# Hum_ADC.net
KiCad netlist of a schematic drawn in Altium Designer
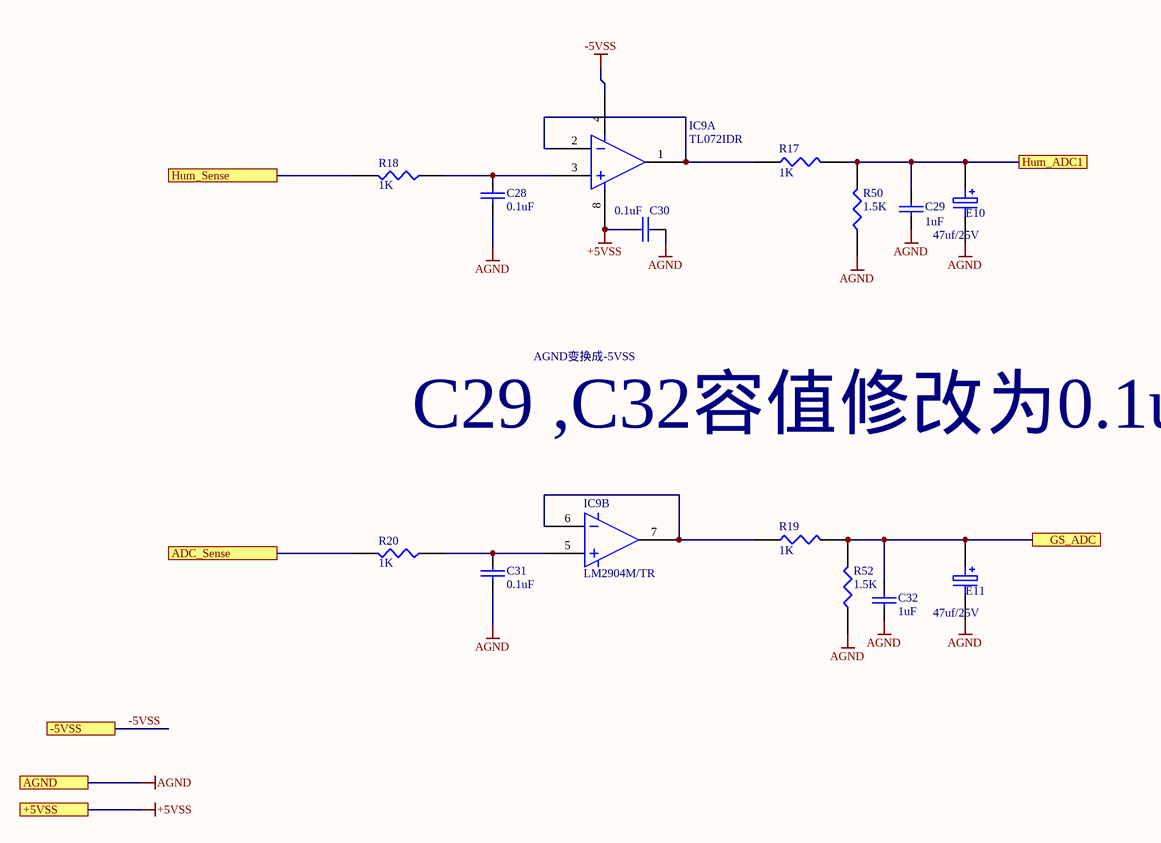
[diagram p0: Hum_ADC.SchDoc]

(export (version "E")
  (design (tool "Eeschema 10.0.6"))
  (components
    (comp (ref "C28")
      (value "0.1uF")
      (footprint "0805C")
      (description "品牌： SAMSUNG(三星) 型号： CL21B104KBCNNNC ：容值：100nF 精度：±10% 额定电压：50V 材质(温度系数)：X7R 材质:X7R")
      (libsource (lib "*") (part "CAP"))
    )
    (comp (ref "C29")
      (value "1uF")
      (footprint "0805C")
      (description "品牌： SAMSUNG(三星) 型号： CL21B104KBCNNNC ：容值：100nF 精度：±10% 额定电压：50V 材质(温度系数)：X7R 材质:X7R")
      (libsource (lib "*") (part "CAP"))
    )
    (comp (ref "C30")
      (value "0.1uF")
      (footprint "0805C")
      (description "品牌： SAMSUNG(三星) 型号： CL21B104KBCNNNC ：容值：100nF 精度：±10% 额定电压：50V 材质(温度系数)：X7R 材质:X7R")
      (libsource (lib "*") (part "CAP"))
    )
    (comp (ref "C31")
      (value "0.1uF")
      (footprint "0805C")
      (description "品牌： SAMSUNG(三星) 型号： CL21B104KBCNNNC ：容值：100nF 精度：±10% 额定电压：50V 材质(温度系数)：X7R 材质:X7R")
      (libsource (lib "*") (part "CAP"))
    )
    (comp (ref "C32")
      (value "1uF")
      (footprint "0805C")
      (description "品牌： SAMSUNG(三星) 型号： CL21B104KBCNNNC ：容值：100nF 精度：±10% 额定电压：50V 材质(温度系数)：X7R 材质:X7R")
      (libsource (lib "*") (part "CAP"))
    )
    (comp (ref "E10")
      (value "47uf/25V")
      (footprint "CAP-TH_BD5.0-P2.00-D0.8-FD")
      (description "品牌： CX(承兴) 型号： KM108M025G17RR0VH2FP0 容值：1000uF 精度：±20% 额定电压：25V")
      (libsource (lib "*") (part "ELECTRO1"))
    )
    (comp (ref "E11")
      (value "47uf/25V")
      (footprint "CAP-TH_BD5.0-P2.00-D0.8-FD")
      (description "品牌： CX(承兴) 型号： KM108M025G17RR0VH2FP0 容值：1000uF 精度：±20% 额定电压：25V")
      (libsource (lib "*") (part "ELECTRO1"))
    )
    (comp (ref "IC9")
      (value "TL072IDR")
      (footprint "LM2904M/TR")
      (description "品牌： HGSEMI(华冠)   型号： LM2904M/TR")
      (libsource (lib "main board fo stk_1") (part "TL072"))
    )
    (comp (ref "R17")
      (value "1K")
      (footprint "0805R")
      (description "品牌： UNI-ROYAL(厚声) 型号： 0805W8F1001T5E 电阻类型：厚膜电阻 阻值：1kΩ 精度：±1% 功率：125mW 温度系数：±100ppm/℃")
      (libsource (lib "*") (part "RES1"))
    )
    (comp (ref "R18")
      (value "1K")
      (footprint "0805R")
      (description "品牌： UNI-ROYAL(厚声) 型号： 0805W8F1001T5E 电阻类型：厚膜电阻 阻值：1kΩ 精度：±1% 功率：125mW 温度系数：±100ppm/℃")
      (libsource (lib "*") (part "RES1"))
    )
    (comp (ref "R19")
      (value "1K")
      (footprint "0805R")
      (description "品牌： UNI-ROYAL(厚声) 型号： 0805W8F1001T5E 电阻类型：厚膜电阻 阻值：1kΩ 精度：±1% 功率：125mW 温度系数：±100ppm/℃")
      (libsource (lib "*") (part "RES1"))
    )
    (comp (ref "R20")
      (value "1K")
      (footprint "0805R")
      (description "品牌： UNI-ROYAL(厚声) 型号： 0805W8F1001T5E 电阻类型：厚膜电阻 阻值：1kΩ 精度：±1% 功率：125mW 温度系数：±100ppm/℃")
      (libsource (lib "*") (part "RES1"))
    )
    (comp (ref "R50")
      (value "1.5K")
      (footprint "0805R")
      (description "品牌： UNI-ROYAL(厚声) 型号： 0805W8F1001T5E 电阻类型：厚膜电阻 阻值：1kΩ 精度：±1% 功率：125mW 温度系数：±100ppm/℃")
      (libsource (lib "*") (part "RES1"))
    )
    (comp (ref "R52")
      (value "1.5K")
      (footprint "0805R")
      (description "品牌： UNI-ROYAL(厚声) 型号： 0805W8F1001T5E 电阻类型：厚膜电阻 阻值：1kΩ 精度：±1% 功率：125mW 温度系数：±100ppm/℃")
      (libsource (lib "*") (part "RES1"))
    )
  )
  (nets
    (net (code "1") (name "+5VSS") (class "Default")
      (node (ref "C30") (pin "2") (pinfunction "2_2") (pintype "passive"))
      (node (ref "IC9") (pin "8") (pintype "passive"))
    )
    (net (code "2") (name "-5VSS") (class "Default") (node (ref "IC9") (pin "4") (pintype "passive")))
    (net (code "3") (name "/ADC_Sense") (class "Default")
      (node (ref "R20") (pin "2") (pinfunction "2_2") (pintype "passive"))
    )
    (net (code "4") (name "/GS_ADC") (class "Default")
      (node (ref "C32") (pin "1") (pinfunction "1_1") (pintype "passive"))
      (node (ref "E11") (pin "1") (pinfunction "1_1") (pintype "passive"))
      (node (ref "R19") (pin "2") (pinfunction "2_2") (pintype "passive"))
      (node (ref "R52") (pin "2") (pinfunction "2_2") (pintype "passive"))
    )
    (net (code "5") (name "/Hum_ADC1") (class "Default")
      (node (ref "C29") (pin "1") (pinfunction "1_1") (pintype "passive"))
      (node (ref "E10") (pin "1") (pinfunction "1_1") (pintype "passive"))
      (node (ref "R17") (pin "2") (pinfunction "2_2") (pintype "passive"))
      (node (ref "R50") (pin "2") (pinfunction "2_2") (pintype "passive"))
    )
    (net (code "6") (name "/Hum_Sense") (class "Default")
      (node (ref "R18") (pin "2") (pinfunction "2_2") (pintype "passive"))
    )
    (net (code "7") (name "AGND") (class "Default")
      (node (ref "C28") (pin "2") (pinfunction "2_2") (pintype "passive"))
      (node (ref "C29") (pin "2") (pinfunction "2_2") (pintype "passive"))
      (node (ref "C30") (pin "1") (pinfunction "1_1") (pintype "passive"))
      (node (ref "C31") (pin "2") (pinfunction "2_2") (pintype "passive"))
      (node (ref "C32") (pin "2") (pinfunction "2_2") (pintype "passive"))
      (node (ref "E10") (pin "2") (pinfunction "2_2") (pintype "passive"))
      (node (ref "E11") (pin "2") (pinfunction "2_2") (pintype "passive"))
      (node (ref "R50") (pin "1") (pinfunction "1_1") (pintype "passive"))
      (node (ref "R52") (pin "1") (pinfunction "1_1") (pintype "passive"))
    )
    (net (code "8") (name "Net-(C28-Pad1)") (class "Default")
      (node (ref "C28") (pin "1") (pinfunction "1_1") (pintype "passive"))
      (node (ref "IC9") (pin "3") (pintype "passive"))
      (node (ref "R18") (pin "1") (pinfunction "1_1") (pintype "passive"))
    )
    (net (code "9") (name "Net-(C31-Pad1)") (class "Default")
      (node (ref "C31") (pin "1") (pinfunction "1_1") (pintype "passive"))
      (node (ref "IC9") (pin "5") (pintype "passive"))
      (node (ref "R20") (pin "1") (pinfunction "1_1") (pintype "passive"))
    )
    (net (code "10") (name "Net-(IC9-Pad1)") (class "Default")
      (node (ref "IC9") (pin "1") (pintype "passive"))
      (node (ref "IC9") (pin "2") (pintype "passive"))
      (node (ref "R17") (pin "1") (pinfunction "1_1") (pintype "passive"))
    )
    (net (code "11") (name "Net-(IC9-Pad6)") (class "Default")
      (node (ref "IC9") (pin "6") (pintype "passive"))
      (node (ref "IC9") (pin "7") (pintype "passive"))
      (node (ref "R19") (pin "1") (pinfunction "1_1") (pintype "passive"))
    )
  )
)
